# STM32_CAN-USB.net
KiCad netlist of a schematic drawn in EAGLE
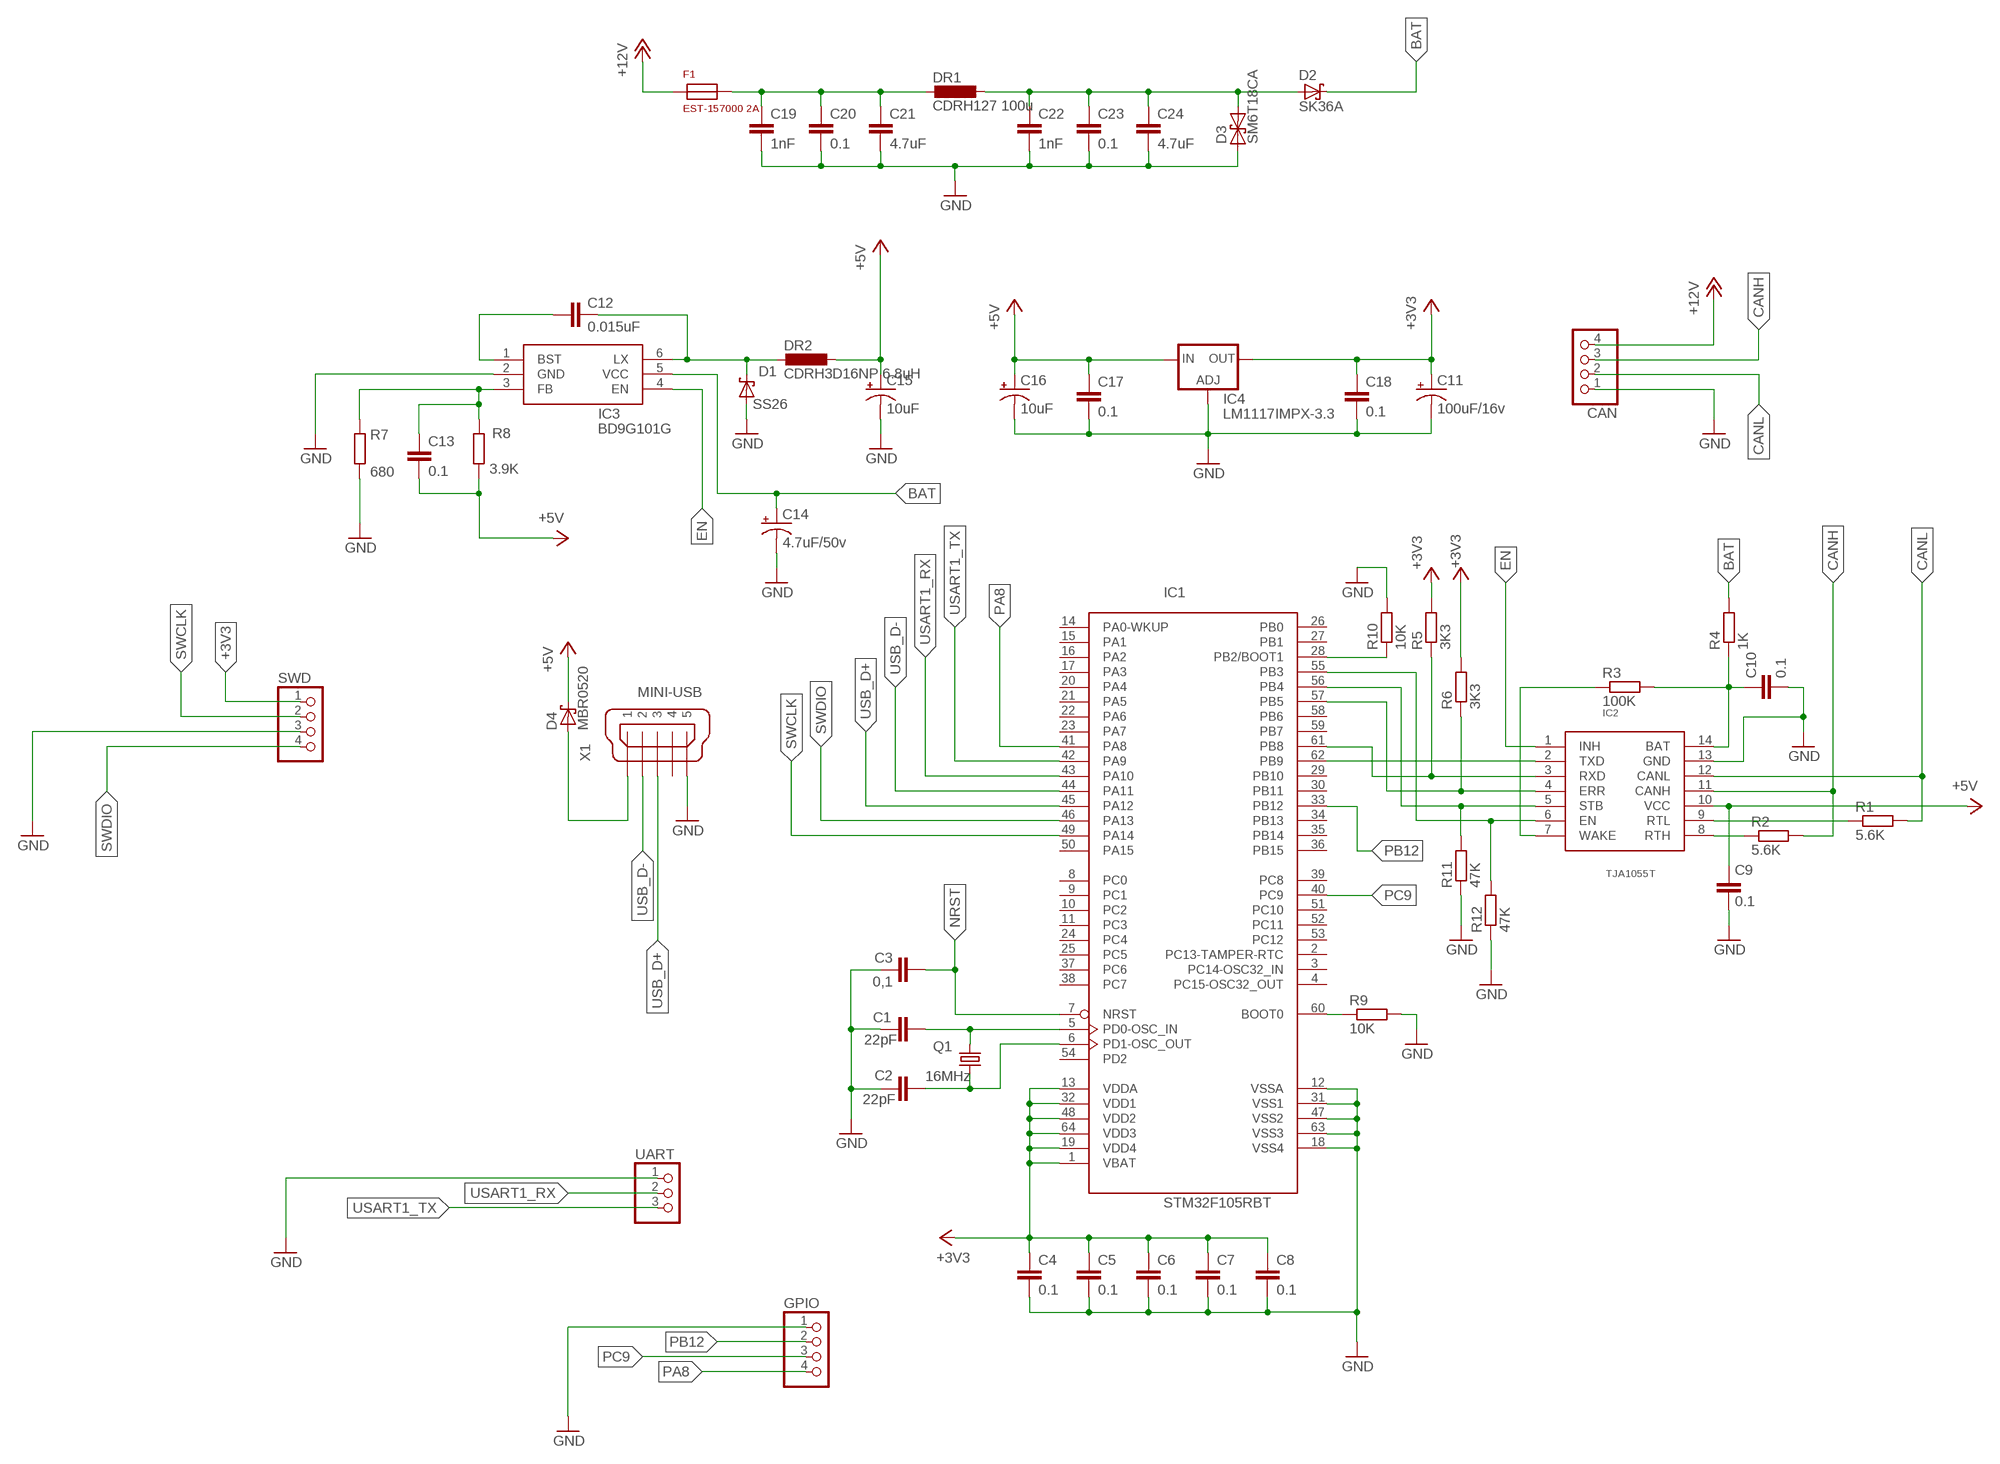
[diagram p0: schematic, sheet 1]

(export (version "E")
  (design (tool "Eeschema 10.0.6"))
  (components
    (comp (ref "C1")
      (value "22pF")
      (footprint "eagle-import:C0805")
      (libsource (lib "eagle-import") (part "C-EUC0805"))
    )
    (comp (ref "C2")
      (value "22pF")
      (footprint "eagle-import:C0805")
      (libsource (lib "eagle-import") (part "C-EUC0805"))
    )
    (comp (ref "C3")
      (value "0,1")
      (footprint "eagle-import:C0805")
      (libsource (lib "eagle-import") (part "C-EUC0805"))
    )
    (comp (ref "C4")
      (value "0.1")
      (footprint "eagle-import:C0805")
      (libsource (lib "eagle-import") (part "C-EUC0805"))
    )
    (comp (ref "C5")
      (value "0.1")
      (footprint "eagle-import:C0805")
      (libsource (lib "eagle-import") (part "C-EUC0805"))
    )
    (comp (ref "C6")
      (value "0.1")
      (footprint "eagle-import:C0805")
      (libsource (lib "eagle-import") (part "C-EUC0805"))
    )
    (comp (ref "C7")
      (value "0.1")
      (footprint "eagle-import:C0805")
      (libsource (lib "eagle-import") (part "C-EUC0805"))
    )
    (comp (ref "C8")
      (value "0.1")
      (footprint "eagle-import:C0805")
      (libsource (lib "eagle-import") (part "C-EUC0805"))
    )
    (comp (ref "C9")
      (value "0.1")
      (footprint "eagle-import:C0805")
      (libsource (lib "eagle-import") (part "C-EUC0805"))
    )
    (comp (ref "C10")
      (value "0.1")
      (footprint "eagle-import:C0805")
      (libsource (lib "eagle-import") (part "C-EUC0805"))
    )
    (comp (ref "C11")
      (value "100uF/16v")
      (footprint "eagle-import:153CLV-0605")
      (libsource (lib "eagle-import") (part "CPOL-US153CLV-0605"))
    )
    (comp (ref "C12")
      (value "0.015uF")
      (footprint "eagle-import:C0805")
      (libsource (lib "eagle-import") (part "C-EUC0805"))
    )
    (comp (ref "C13")
      (value "0.1")
      (footprint "eagle-import:C0805")
      (libsource (lib "eagle-import") (part "C-EUC0805"))
    )
    (comp (ref "C14")
      (value "4.7uF/50v")
      (footprint "eagle-import:153CLV-0605")
      (libsource (lib "eagle-import") (part "CPOL-US153CLV-0605"))
    )
    (comp (ref "C15")
      (value "10uF")
      (footprint "eagle-import:153CLV-0605")
      (libsource (lib "eagle-import") (part "CPOL-US153CLV-0605"))
    )
    (comp (ref "C16")
      (value "10uF")
      (footprint "eagle-import:153CLV-0605")
      (libsource (lib "eagle-import") (part "CPOL-US153CLV-0605"))
    )
    (comp (ref "C17")
      (value "0.1")
      (footprint "eagle-import:C0805")
      (libsource (lib "eagle-import") (part "C-EUC0805"))
    )
    (comp (ref "C18")
      (value "0.1")
      (footprint "eagle-import:C0805")
      (libsource (lib "eagle-import") (part "C-EUC0805"))
    )
    (comp (ref "C19")
      (value "1nF")
      (footprint "eagle-import:C0805")
      (libsource (lib "eagle-import") (part "C-EUC0805"))
    )
    (comp (ref "C20")
      (value "0.1")
      (footprint "eagle-import:C0805")
      (libsource (lib "eagle-import") (part "C-EUC0805"))
    )
    (comp (ref "C21")
      (value "4.7uF")
      (footprint "eagle-import:C0805")
      (libsource (lib "eagle-import") (part "C-EUC0805"))
    )
    (comp (ref "C22")
      (value "1nF")
      (footprint "eagle-import:C0805")
      (libsource (lib "eagle-import") (part "C-EUC0805"))
    )
    (comp (ref "C23")
      (value "0.1")
      (footprint "eagle-import:C0805")
      (libsource (lib "eagle-import") (part "C-EUC0805"))
    )
    (comp (ref "C24")
      (value "4.7uF")
      (footprint "eagle-import:C0805")
      (libsource (lib "eagle-import") (part "C-EUC0805"))
    )
    (comp (ref "CAN")
      (value "PINHD-1X4")
      (footprint "eagle-import:1X04")
      (libsource (lib "eagle-import") (part "PINHD-1X4"))
    )
    (comp (ref "D1")
      (value "SS26")
      (footprint "eagle-import:SMB")
      (libsource (lib "eagle-import") (part "SCHOTTKY-DIODESMD"))
    )
    (comp (ref "D2")
      (value "SK36A")
      (footprint "eagle-import:DO-214AC")
      (libsource (lib "eagle-import") (part "SK36A"))
    )
    (comp (ref "D3")
      (value "SM6T18CA")
      (footprint "eagle-import:DO214AA")
      (libsource (lib "eagle-import") (part "SM6T18CA"))
    )
    (comp (ref "D4")
      (value "MBR0520")
      (footprint "eagle-import:SOD123")
      (libsource (lib "eagle-import") (part "MBR0520"))
    )
    (comp (ref "DR1")
      (value "CDRH127 100u")
      (footprint "eagle-import:MS85")
      (libsource (lib "eagle-import") (part "CDRH127"))
    )
    (comp (ref "DR2")
      (value "CDRH3D16NP 6.8uH")
      (footprint "eagle-import:CDRH3D16NP")
      (libsource (lib "eagle-import") (part "CDRH3D16NP"))
    )
    (comp (ref "F1")
      (value "EST-157000 2A")
      (footprint "eagle-import:FUSE")
      (libsource (lib "eagle-import") (part "FUSE"))
    )
    (comp (ref "GPIO")
      (value "PINHD-1X4")
      (footprint "eagle-import:1X04")
      (libsource (lib "eagle-import") (part "PINHD-1X4"))
    )
    (comp (ref "IC1")
      (value "STM32F105RBT")
      (footprint "eagle-import:LQFP64")
      (libsource (lib "eagle-import") (part "STM32F105RTB"))
    )
    (comp (ref "IC2")
      (value "TJA1055T")
      (footprint "eagle-import:SO-14W")
      (libsource (lib "eagle-import") (part "TJA1054T"))
    )
    (comp (ref "IC3")
      (value "BD9G101G")
      (footprint "eagle-import:SSOP6")
      (libsource (lib "eagle-import") (part "BD9G101G"))
    )
    (comp (ref "IC4")
      (value "LM1117IMPX-3.3")
      (footprint "eagle-import:SOT223")
      (libsource (lib "eagle-import") (part "LM1117IMPX-3.3"))
    )
    (comp (ref "Q1")
      (value "16MHz")
      (footprint "eagle-import:HC49UP")
      (libsource (lib "eagle-import") (part "CRYSTALHC49UP"))
    )
    (comp (ref "R1")
      (value "5.6K")
      (footprint "eagle-import:R0805")
      (libsource (lib "eagle-import") (part "R-EU_R0805"))
    )
    (comp (ref "R2")
      (value "5.6K")
      (footprint "eagle-import:R0805")
      (libsource (lib "eagle-import") (part "R-EU_R0805"))
    )
    (comp (ref "R3")
      (value "100K")
      (footprint "eagle-import:R0805")
      (libsource (lib "eagle-import") (part "R-EU_R0805"))
    )
    (comp (ref "R4")
      (value "1K")
      (footprint "eagle-import:R0805")
      (libsource (lib "eagle-import") (part "R-EU_R0805"))
    )
    (comp (ref "R5")
      (value "3K3")
      (footprint "eagle-import:R0805")
      (libsource (lib "eagle-import") (part "R-EU_R0805"))
    )
    (comp (ref "R6")
      (value "3K3")
      (footprint "eagle-import:R0805")
      (libsource (lib "eagle-import") (part "R-EU_R0805"))
    )
    (comp (ref "R7")
      (value "680")
      (footprint "eagle-import:R0805")
      (libsource (lib "eagle-import") (part "R-EU_R0805"))
    )
    (comp (ref "R8")
      (value "3.9K")
      (footprint "eagle-import:R0805")
      (libsource (lib "eagle-import") (part "R-EU_R0805"))
    )
    (comp (ref "R9")
      (value "10K")
      (footprint "eagle-import:R0805")
      (libsource (lib "eagle-import") (part "R-EU_R0805"))
    )
    (comp (ref "R10")
      (value "10K")
      (footprint "eagle-import:R0805")
      (libsource (lib "eagle-import") (part "R-EU_R0805"))
    )
    (comp (ref "R11")
      (value "47K")
      (footprint "eagle-import:R0805")
      (libsource (lib "eagle-import") (part "R-EU_R0805"))
    )
    (comp (ref "R12")
      (value "47K")
      (footprint "eagle-import:R0805")
      (libsource (lib "eagle-import") (part "R-EU_R0805"))
    )
    (comp (ref "SWD")
      (value "PINHD-1X4")
      (footprint "eagle-import:1X04")
      (libsource (lib "eagle-import") (part "PINHD-1X4"))
    )
    (comp (ref "UART")
      (value "PINHD-1X3")
      (footprint "eagle-import:1X03")
      (libsource (lib "eagle-import") (part "PINHD-1X3"))
    )
    (comp (ref "X1")
      (value "MINI-USB")
      (footprint "eagle-import:UX60-MB-5ST")
      (libsource (lib "eagle-import") (part "MINI-USB-UX60-MB-5ST"))
    )
  )
  (nets
    (net (code "1") (name "+3V3") (class "Default")
      (node (ref "C11") (pin "+") (pinfunction "+_+") (pintype "passive"))
      (node (ref "C18") (pin "1") (pinfunction "1_1") (pintype "passive"))
      (node (ref "C4") (pin "1") (pinfunction "1_1") (pintype "passive"))
      (node (ref "C5") (pin "1") (pinfunction "1_1") (pintype "passive"))
      (node (ref "C6") (pin "1") (pinfunction "1_1") (pintype "passive"))
      (node (ref "C7") (pin "1") (pinfunction "1_1") (pintype "passive"))
      (node (ref "C8") (pin "1") (pinfunction "1_1") (pintype "passive"))
      (node (ref "IC1") (pin "1") (pinfunction "VBAT_1") (pintype "power_in"))
      (node (ref "IC1") (pin "13") (pinfunction "VDDA_13") (pintype "power_in"))
      (node (ref "IC1") (pin "19") (pinfunction "VDD4_19") (pintype "power_in"))
      (node (ref "IC1") (pin "32") (pinfunction "VDD1_32") (pintype "power_in"))
      (node (ref "IC1") (pin "48") (pinfunction "VDD2_48") (pintype "power_in"))
      (node (ref "IC1") (pin "64") (pinfunction "VDD3_64") (pintype "power_in"))
      (node (ref "IC4") (pin "2") (pinfunction "OUT_2") (pintype "passive"))
      (node (ref "IC4") (pin "4") (pinfunction "OUT_4") (pintype "passive"))
      (node (ref "R5") (pin "2") (pinfunction "2_2") (pintype "passive"))
      (node (ref "R6") (pin "2") (pinfunction "2_2") (pintype "passive"))
      (node (ref "SWD") (pin "1") (pinfunction "1_1") (pintype "passive"))
    )
    (net (code "2") (name "+5V") (class "Default")
      (node (ref "C13") (pin "2") (pinfunction "2_2") (pintype "passive"))
      (node (ref "C15") (pin "+") (pinfunction "+_+") (pintype "passive"))
      (node (ref "C16") (pin "+") (pinfunction "+_+") (pintype "passive"))
      (node (ref "C17") (pin "1") (pinfunction "1_1") (pintype "passive"))
      (node (ref "C9") (pin "1") (pinfunction "1_1") (pintype "passive"))
      (node (ref "D4") (pin "C") (pinfunction "C_C") (pintype "passive"))
      (node (ref "DR2") (pin "P$2") (pinfunction "2_P$2") (pintype "passive"))
      (node (ref "IC2") (pin "10") (pinfunction "VCC_10") (pintype "power_in"))
      (node (ref "IC4") (pin "3") (pinfunction "IN_3") (pintype "input"))
      (node (ref "R8") (pin "1") (pinfunction "1_1") (pintype "passive"))
    )
    (net (code "3") (name "+12V") (class "Default")
      (node (ref "CAN") (pin "4") (pinfunction "4_4") (pintype "passive"))
      (node (ref "F1") (pin "P$1") (pinfunction "1_P$1") (pintype "power_in"))
    )
    (net (code "4") (name "BAT") (class "Default")
      (node (ref "C14") (pin "+") (pinfunction "+_+") (pintype "passive"))
      (node (ref "D2") (pin "C") (pinfunction "C_C") (pintype "passive"))
      (node (ref "IC3") (pin "5") (pinfunction "VCC_5") (pintype "power_in"))
      (node (ref "R4") (pin "2") (pinfunction "2_2") (pintype "passive"))
    )
    (net (code "5") (name "CANH") (class "Default")
      (node (ref "CAN") (pin "3") (pinfunction "3_3") (pintype "passive"))
      (node (ref "IC2") (pin "11") (pinfunction "CANH_11") (pintype "bidirectional"))
      (node (ref "R2") (pin "2") (pinfunction "2_2") (pintype "passive"))
    )
    (net (code "6") (name "CANL") (class "Default")
      (node (ref "CAN") (pin "2") (pinfunction "2_2") (pintype "passive"))
      (node (ref "IC2") (pin "12") (pinfunction "CANL_12") (pintype "bidirectional"))
      (node (ref "R1") (pin "2") (pinfunction "2_2") (pintype "passive"))
    )
    (net (code "7") (name "EN") (class "Default")
      (node (ref "IC2") (pin "1") (pinfunction "INH_1") (pintype "output"))
      (node (ref "IC3") (pin "4") (pinfunction "EN_4") (pintype "input"))
    )
    (net (code "8") (name "GND") (class "Default")
      (node (ref "C1") (pin "2") (pinfunction "2_2") (pintype "passive"))
      (node (ref "C10") (pin "2") (pinfunction "2_2") (pintype "passive"))
      (node (ref "C11") (pin "-") (pinfunction "-_-") (pintype "passive"))
      (node (ref "C14") (pin "-") (pinfunction "-_-") (pintype "passive"))
      (node (ref "C15") (pin "-") (pinfunction "-_-") (pintype "passive"))
      (node (ref "C16") (pin "-") (pinfunction "-_-") (pintype "passive"))
      (node (ref "C17") (pin "2") (pinfunction "2_2") (pintype "passive"))
      (node (ref "C18") (pin "2") (pinfunction "2_2") (pintype "passive"))
      (node (ref "C19") (pin "2") (pinfunction "2_2") (pintype "passive"))
      (node (ref "C2") (pin "2") (pinfunction "2_2") (pintype "passive"))
      (node (ref "C20") (pin "2") (pinfunction "2_2") (pintype "passive"))
      (node (ref "C21") (pin "2") (pinfunction "2_2") (pintype "passive"))
      (node (ref "C22") (pin "2") (pinfunction "2_2") (pintype "passive"))
      (node (ref "C23") (pin "2") (pinfunction "2_2") (pintype "passive"))
      (node (ref "C24") (pin "2") (pinfunction "2_2") (pintype "passive"))
      (node (ref "C3") (pin "1") (pinfunction "1_1") (pintype "passive"))
      (node (ref "C4") (pin "2") (pinfunction "2_2") (pintype "passive"))
      (node (ref "C5") (pin "2") (pinfunction "2_2") (pintype "passive"))
      (node (ref "C6") (pin "2") (pinfunction "2_2") (pintype "passive"))
      (node (ref "C7") (pin "2") (pinfunction "2_2") (pintype "passive"))
      (node (ref "C8") (pin "2") (pinfunction "2_2") (pintype "passive"))
      (node (ref "C9") (pin "2") (pinfunction "2_2") (pintype "passive"))
      (node (ref "CAN") (pin "1") (pinfunction "1_1") (pintype "passive"))
      (node (ref "D1") (pin "A") (pinfunction "A_A") (pintype "passive"))
      (node (ref "D3") (pin "A") (pinfunction "1_A") (pintype "passive"))
      (node (ref "GPIO") (pin "1") (pinfunction "1_1") (pintype "passive"))
      (node (ref "IC1") (pin "12") (pinfunction "VSSA_12") (pintype "power_in"))
      (node (ref "IC1") (pin "18") (pinfunction "VSS4_18") (pintype "power_in"))
      (node (ref "IC1") (pin "31") (pinfunction "VSS1_31") (pintype "power_in"))
      (node (ref "IC1") (pin "47") (pinfunction "VSS2_47") (pintype "power_in"))
      (node (ref "IC1") (pin "63") (pinfunction "VSS3_63") (pintype "power_in"))
      (node (ref "IC2") (pin "13") (pinfunction "GND_13") (pintype "power_in"))
      (node (ref "IC3") (pin "2") (pinfunction "GND_2") (pintype "power_in"))
      (node (ref "IC4") (pin "1") (pinfunction "ADJ_1") (pintype "input"))
      (node (ref "R10") (pin "2") (pinfunction "2_2") (pintype "passive"))
      (node (ref "R11") (pin "1") (pinfunction "1_1") (pintype "passive"))
      (node (ref "R12") (pin "1") (pinfunction "1_1") (pintype "passive"))
      (node (ref "R7") (pin "1") (pinfunction "1_1") (pintype "passive"))
      (node (ref "R9") (pin "2") (pinfunction "2_2") (pintype "passive"))
      (node (ref "SWD") (pin "3") (pinfunction "3_3") (pintype "passive"))
      (node (ref "UART") (pin "1") (pinfunction "1_1") (pintype "passive"))
      (node (ref "X1") (pin "5") (pinfunction "5_5") (pintype "input"))
      (node (ref "X1") (pin "M1") (pinfunction "5_M1") (pintype "input"))
      (node (ref "X1") (pin "M2") (pinfunction "5_M2") (pintype "input"))
    )
    (net (code "9") (name "NRST") (class "Default")
      (node (ref "C3") (pin "2") (pinfunction "2_2") (pintype "passive"))
      (node (ref "IC1") (pin "7") (pinfunction "NRST_7") (pintype "bidirectional"))
    )
    (net (code "10") (name "Net-(D3-2)") (class "Default")
      (node (ref "C22") (pin "1") (pinfunction "1_1") (pintype "passive"))
      (node (ref "C23") (pin "1") (pinfunction "1_1") (pintype "passive"))
      (node (ref "C24") (pin "1") (pinfunction "1_1") (pintype "passive"))
      (node (ref "D2") (pin "A") (pinfunction "A_A") (pintype "passive"))
      (node (ref "D3") (pin "C") (pinfunction "2_C") (pintype "passive"))
      (node (ref "DR1") (pin "P$2") (pinfunction "2_P$2") (pintype "passive"))
    )
    (net (code "11") (name "Net-(D4-PadA)") (class "Default")
      (node (ref "D4") (pin "A") (pinfunction "A_A") (pintype "passive"))
      (node (ref "X1") (pin "1") (pinfunction "1_1") (pintype "input"))
    )
    (net (code "12") (name "Net-(DR1-1)") (class "Default")
      (node (ref "C19") (pin "1") (pinfunction "1_1") (pintype "passive"))
      (node (ref "C20") (pin "1") (pinfunction "1_1") (pintype "passive"))
      (node (ref "C21") (pin "1") (pinfunction "1_1") (pintype "passive"))
      (node (ref "DR1") (pin "P$1") (pinfunction "1_P$1") (pintype "passive"))
      (node (ref "F1") (pin "P$2") (pinfunction "2_P$2") (pintype "passive"))
    )
    (net (code "13") (name "Net-(DR2-1)") (class "Default")
      (node (ref "C12") (pin "2") (pinfunction "2_2") (pintype "passive"))
      (node (ref "D1") (pin "C") (pinfunction "C_C") (pintype "passive"))
      (node (ref "DR2") (pin "P$1") (pinfunction "1_P$1") (pintype "passive"))
      (node (ref "IC3") (pin "6") (pinfunction "LX_6") (pintype "output"))
    )
    (net (code "14") (name "Net-(IC1-BOOT0)") (class "Default")
      (node (ref "IC1") (pin "60") (pinfunction "BOOT0_60") (pintype "input"))
      (node (ref "R9") (pin "1") (pinfunction "1_1") (pintype "passive"))
    )
    (net (code "15") (name "Net-(IC1-PB2{slash}BOOT1)") (class "Default")
      (node (ref "IC1") (pin "28") (pinfunction "PB2/BOOT1_28") (pintype "bidirectional"))
      (node (ref "R10") (pin "1") (pinfunction "1_1") (pintype "passive"))
    )
    (net (code "16") (name "Net-(IC1-PB3)") (class "Default")
      (node (ref "IC1") (pin "55") (pinfunction "PB3_55") (pintype "bidirectional"))
      (node (ref "IC2") (pin "6") (pinfunction "EN_6") (pintype "input"))
      (node (ref "R12") (pin "2") (pinfunction "2_2") (pintype "passive"))
    )
    (net (code "17") (name "Net-(IC1-PB4)") (class "Default")
      (node (ref "IC1") (pin "56") (pinfunction "PB4_56") (pintype "bidirectional"))
      (node (ref "IC2") (pin "5") (pinfunction "STB_5") (pintype "input"))
      (node (ref "R11") (pin "2") (pinfunction "2_2") (pintype "passive"))
    )
    (net (code "18") (name "Net-(IC1-PB5)") (class "Default")
      (node (ref "IC1") (pin "57") (pinfunction "PB5_57") (pintype "bidirectional"))
      (node (ref "IC2") (pin "4") (pinfunction "ERR_4") (pintype "output"))
      (node (ref "R6") (pin "1") (pinfunction "1_1") (pintype "passive"))
    )
    (net (code "19") (name "Net-(IC1-PB8)") (class "Default")
      (node (ref "IC1") (pin "61") (pinfunction "PB8_61") (pintype "bidirectional"))
      (node (ref "IC2") (pin "3") (pinfunction "RXD_3") (pintype "bidirectional"))
      (node (ref "R5") (pin "1") (pinfunction "1_1") (pintype "passive"))
    )
    (net (code "20") (name "Net-(IC1-PB9)") (class "Default")
      (node (ref "IC1") (pin "62") (pinfunction "PB9_62") (pintype "bidirectional"))
      (node (ref "IC2") (pin "2") (pinfunction "TXD_2") (pintype "bidirectional"))
    )
    (net (code "21") (name "Net-(IC1-PD0-OSC_IN)") (class "Default")
      (node (ref "C1") (pin "1") (pinfunction "1_1") (pintype "passive"))
      (node (ref "IC1") (pin "5") (pinfunction "PD0-OSC_IN_5") (pintype "bidirectional"))
      (node (ref "Q1") (pin "2") (pinfunction "2_2") (pintype "passive"))
    )
    (net (code "22") (name "Net-(IC1-PD1-OSC_OUT)") (class "Default")
      (node (ref "C2") (pin "1") (pinfunction "1_1") (pintype "passive"))
      (node (ref "IC1") (pin "6") (pinfunction "PD1-OSC_OUT_6") (pintype "bidirectional"))
      (node (ref "Q1") (pin "1") (pinfunction "1_1") (pintype "passive"))
    )
    (net (code "23") (name "Net-(IC2-BAT)") (class "Default")
      (node (ref "C10") (pin "1") (pinfunction "1_1") (pintype "passive"))
      (node (ref "IC2") (pin "14") (pinfunction "BAT_14") (pintype "input"))
      (node (ref "R3") (pin "2") (pinfunction "2_2") (pintype "passive"))
      (node (ref "R4") (pin "1") (pinfunction "1_1") (pintype "passive"))
    )
    (net (code "24") (name "Net-(IC2-RTH)") (class "Default")
      (node (ref "IC2") (pin "8") (pinfunction "RTH_8") (pintype "bidirectional"))
      (node (ref "R2") (pin "1") (pinfunction "1_1") (pintype "passive"))
    )
    (net (code "25") (name "Net-(IC2-RTL)") (class "Default")
      (node (ref "IC2") (pin "9") (pinfunction "RTL_9") (pintype "bidirectional"))
      (node (ref "R1") (pin "1") (pinfunction "1_1") (pintype "passive"))
    )
    (net (code "26") (name "Net-(IC2-WAKE)") (class "Default")
      (node (ref "IC2") (pin "7") (pinfunction "WAKE_7") (pintype "input"))
      (node (ref "R3") (pin "1") (pinfunction "1_1") (pintype "passive"))
    )
    (net (code "27") (name "Net-(IC3-BST)") (class "Default")
      (node (ref "C12") (pin "1") (pinfunction "1_1") (pintype "passive"))
      (node (ref "IC3") (pin "1") (pinfunction "BST_1") (pintype "input"))
    )
    (net (code "28") (name "Net-(IC3-FB)") (class "Default")
      (node (ref "C13") (pin "1") (pinfunction "1_1") (pintype "passive"))
      (node (ref "IC3") (pin "3") (pinfunction "FB_3") (pintype "input"))
      (node (ref "R7") (pin "2") (pinfunction "2_2") (pintype "passive"))
      (node (ref "R8") (pin "2") (pinfunction "2_2") (pintype "passive"))
    )
    (net (code "29") (name "PA8") (class "Default")
      (node (ref "GPIO") (pin "4") (pinfunction "4_4") (pintype "passive"))
      (node (ref "IC1") (pin "41") (pinfunction "PA8_41") (pintype "bidirectional"))
    )
    (net (code "30") (name "PB12") (class "Default")
      (node (ref "GPIO") (pin "2") (pinfunction "2_2") (pintype "passive"))
      (node (ref "IC1") (pin "33") (pinfunction "PB12_33") (pintype "bidirectional"))
    )
    (net (code "31") (name "PC9") (class "Default")
      (node (ref "GPIO") (pin "3") (pinfunction "3_3") (pintype "passive"))
      (node (ref "IC1") (pin "40") (pinfunction "PC9_40") (pintype "bidirectional"))
    )
    (net (code "32") (name "SWCLK") (class "Default")
      (node (ref "IC1") (pin "49") (pinfunction "PA14_49") (pintype "bidirectional"))
      (node (ref "SWD") (pin "2") (pinfunction "2_2") (pintype "passive"))
    )
    (net (code "33") (name "SWDIO") (class "Default")
      (node (ref "IC1") (pin "46") (pinfunction "PA13_46") (pintype "bidirectional"))
      (node (ref "SWD") (pin "4") (pinfunction "4_4") (pintype "passive"))
    )
    (net (code "34") (name "USART1_RX") (class "Default")
      (node (ref "IC1") (pin "43") (pinfunction "PA10_43") (pintype "bidirectional"))
      (node (ref "UART") (pin "2") (pinfunction "2_2") (pintype "passive"))
    )
    (net (code "35") (name "USART1_TX") (class "Default")
      (node (ref "IC1") (pin "42") (pinfunction "PA9_42") (pintype "bidirectional"))
      (node (ref "UART") (pin "3") (pinfunction "3_3") (pintype "passive"))
    )
    (net (code "36") (name "USB_D+") (class "Default")
      (node (ref "IC1") (pin "45") (pinfunction "PA12_45") (pintype "bidirectional"))
      (node (ref "X1") (pin "3") (pinfunction "3_3") (pintype "input"))
    )
    (net (code "37") (name "USB_D-") (class "Default")
      (node (ref "IC1") (pin "44") (pinfunction "PA11_44") (pintype "bidirectional"))
      (node (ref "X1") (pin "2") (pinfunction "2_2") (pintype "input"))
    )
    (net (code "38") (name "unconnected-(IC1-PA0-WKUP-Pad14)") (class "Default")
      (node (ref "IC1") (pin "14") (pinfunction "PA0-WKUP_14") (pintype "bidirectional"))
    )
    (net (code "39") (name "unconnected-(IC1-PA1-Pad15)") (class "Default")
      (node (ref "IC1") (pin "15") (pinfunction "PA1_15") (pintype "bidirectional"))
    )
    (net (code "40") (name "unconnected-(IC1-PA2-Pad16)") (class "Default")
      (node (ref "IC1") (pin "16") (pinfunction "PA2_16") (pintype "bidirectional"))
    )
    (net (code "41") (name "unconnected-(IC1-PA3-Pad17)") (class "Default")
      (node (ref "IC1") (pin "17") (pinfunction "PA3_17") (pintype "bidirectional"))
    )
    (net (code "42") (name "unconnected-(IC1-PA4-Pad20)") (class "Default")
      (node (ref "IC1") (pin "20") (pinfunction "PA4_20") (pintype "bidirectional"))
    )
    (net (code "43") (name "unconnected-(IC1-PA5-Pad21)") (class "Default")
      (node (ref "IC1") (pin "21") (pinfunction "PA5_21") (pintype "bidirectional"))
    )
    (net (code "44") (name "unconnected-(IC1-PA6-Pad22)") (class "Default")
      (node (ref "IC1") (pin "22") (pinfunction "PA6_22") (pintype "bidirectional"))
    )
    (net (code "45") (name "unconnected-(IC1-PA7-Pad23)") (class "Default")
      (node (ref "IC1") (pin "23") (pinfunction "PA7_23") (pintype "bidirectional"))
    )
    (net (code "46") (name "unconnected-(IC1-PA15-Pad50)") (class "Default")
      (node (ref "IC1") (pin "50") (pinfunction "PA15_50") (pintype "bidirectional"))
    )
    (net (code "47") (name "unconnected-(IC1-PB0-Pad26)") (class "Default")
      (node (ref "IC1") (pin "26") (pinfunction "PB0_26") (pintype "bidirectional"))
    )
    (net (code "48") (name "unconnected-(IC1-PB1-Pad27)") (class "Default")
      (node (ref "IC1") (pin "27") (pinfunction "PB1_27") (pintype "bidirectional"))
    )
    (net (code "49") (name "unconnected-(IC1-PB6-Pad58)") (class "Default")
      (node (ref "IC1") (pin "58") (pinfunction "PB6_58") (pintype "bidirectional"))
    )
    (net (code "50") (name "unconnected-(IC1-PB7-Pad59)") (class "Default")
      (node (ref "IC1") (pin "59") (pinfunction "PB7_59") (pintype "bidirectional"))
    )
    (net (code "51") (name "unconnected-(IC1-PB10-Pad29)") (class "Default")
      (node (ref "IC1") (pin "29") (pinfunction "PB10_29") (pintype "bidirectional"))
    )
    (net (code "52") (name "unconnected-(IC1-PB11-Pad30)") (class "Default")
      (node (ref "IC1") (pin "30") (pinfunction "PB11_30") (pintype "bidirectional"))
    )
    (net (code "53") (name "unconnected-(IC1-PB13-Pad34)") (class "Default")
      (node (ref "IC1") (pin "34") (pinfunction "PB13_34") (pintype "bidirectional"))
    )
    (net (code "54") (name "unconnected-(IC1-PB14-Pad35)") (class "Default")
      (node (ref "IC1") (pin "35") (pinfunction "PB14_35") (pintype "bidirectional"))
    )
    (net (code "55") (name "unconnected-(IC1-PB15-Pad36)") (class "Default")
      (node (ref "IC1") (pin "36") (pinfunction "PB15_36") (pintype "bidirectional"))
    )
    (net (code "56") (name "unconnected-(IC1-PC0-Pad8)") (class "Default")
      (node (ref "IC1") (pin "8") (pinfunction "PC0_8") (pintype "bidirectional"))
    )
    (net (code "57") (name "unconnected-(IC1-PC1-Pad9)") (class "Default")
      (node (ref "IC1") (pin "9") (pinfunction "PC1_9") (pintype "bidirectional"))
    )
    (net (code "58") (name "unconnected-(IC1-PC2-Pad10)") (class "Default")
      (node (ref "IC1") (pin "10") (pinfunction "PC2_10") (pintype "bidirectional"))
    )
    (net (code "59") (name "unconnected-(IC1-PC3-Pad11)") (class "Default")
      (node (ref "IC1") (pin "11") (pinfunction "PC3_11") (pintype "bidirectional"))
    )
    (net (code "60") (name "unconnected-(IC1-PC4-Pad24)") (class "Default")
      (node (ref "IC1") (pin "24") (pinfunction "PC4_24") (pintype "bidirectional"))
    )
    (net (code "61") (name "unconnected-(IC1-PC5-Pad25)") (class "Default")
      (node (ref "IC1") (pin "25") (pinfunction "PC5_25") (pintype "bidirectional"))
    )
    (net (code "62") (name "unconnected-(IC1-PC6-Pad37)") (class "Default")
      (node (ref "IC1") (pin "37") (pinfunction "PC6_37") (pintype "bidirectional"))
    )
    (net (code "63") (name "unconnected-(IC1-PC7-Pad38)") (class "Default")
      (node (ref "IC1") (pin "38") (pinfunction "PC7_38") (pintype "bidirectional"))
    )
    (net (code "64") (name "unconnected-(IC1-PC8-Pad39)") (class "Default")
      (node (ref "IC1") (pin "39") (pinfunction "PC8_39") (pintype "bidirectional"))
    )
    (net (code "65") (name "unconnected-(IC1-PC10-Pad51)") (class "Default")
      (node (ref "IC1") (pin "51") (pinfunction "PC10_51") (pintype "bidirectional"))
    )
    (net (code "66") (name "unconnected-(IC1-PC11-Pad52)") (class "Default")
      (node (ref "IC1") (pin "52") (pinfunction "PC11_52") (pintype "bidirectional"))
    )
    (net (code "67") (name "unconnected-(IC1-PC12-Pad53)") (class "Default")
      (node (ref "IC1") (pin "53") (pinfunction "PC12_53") (pintype "bidirectional"))
    )
    (net (code "68") (name "unconnected-(IC1-PC13-TAMPER-RTC-Pad2)") (class "Default")
      (node (ref "IC1") (pin "2") (pinfunction "PC13-TAMPER-RTC_2") (pintype "bidirectional"))
    )
    (net (code "69") (name "unconnected-(IC1-PC14-OSC32_IN-Pad3)") (class "Default")
      (node (ref "IC1") (pin "3") (pinfunction "PC14-OSC32_IN_3") (pintype "bidirectional"))
    )
    (net (code "70") (name "unconnected-(IC1-PC15-OSC32_OUT-Pad4)") (class "Default")
      (node (ref "IC1") (pin "4") (pinfunction "PC15-OSC32_OUT_4") (pintype "bidirectional"))
    )
    (net (code "71") (name "unconnected-(IC1-PD2-Pad54)") (class "Default")
      (node (ref "IC1") (pin "54") (pinfunction "PD2_54") (pintype "bidirectional"))
    )
    (net (code "72") (name "unconnected-(X1-Pad4)") (class "Default")
      (node (ref "X1") (pin "4") (pinfunction "4_4") (pintype "input"))
    )
  )
)
